# Tinyusbboard_rev4_THT.net
KiCad netlist of a schematic drawn in EAGLE
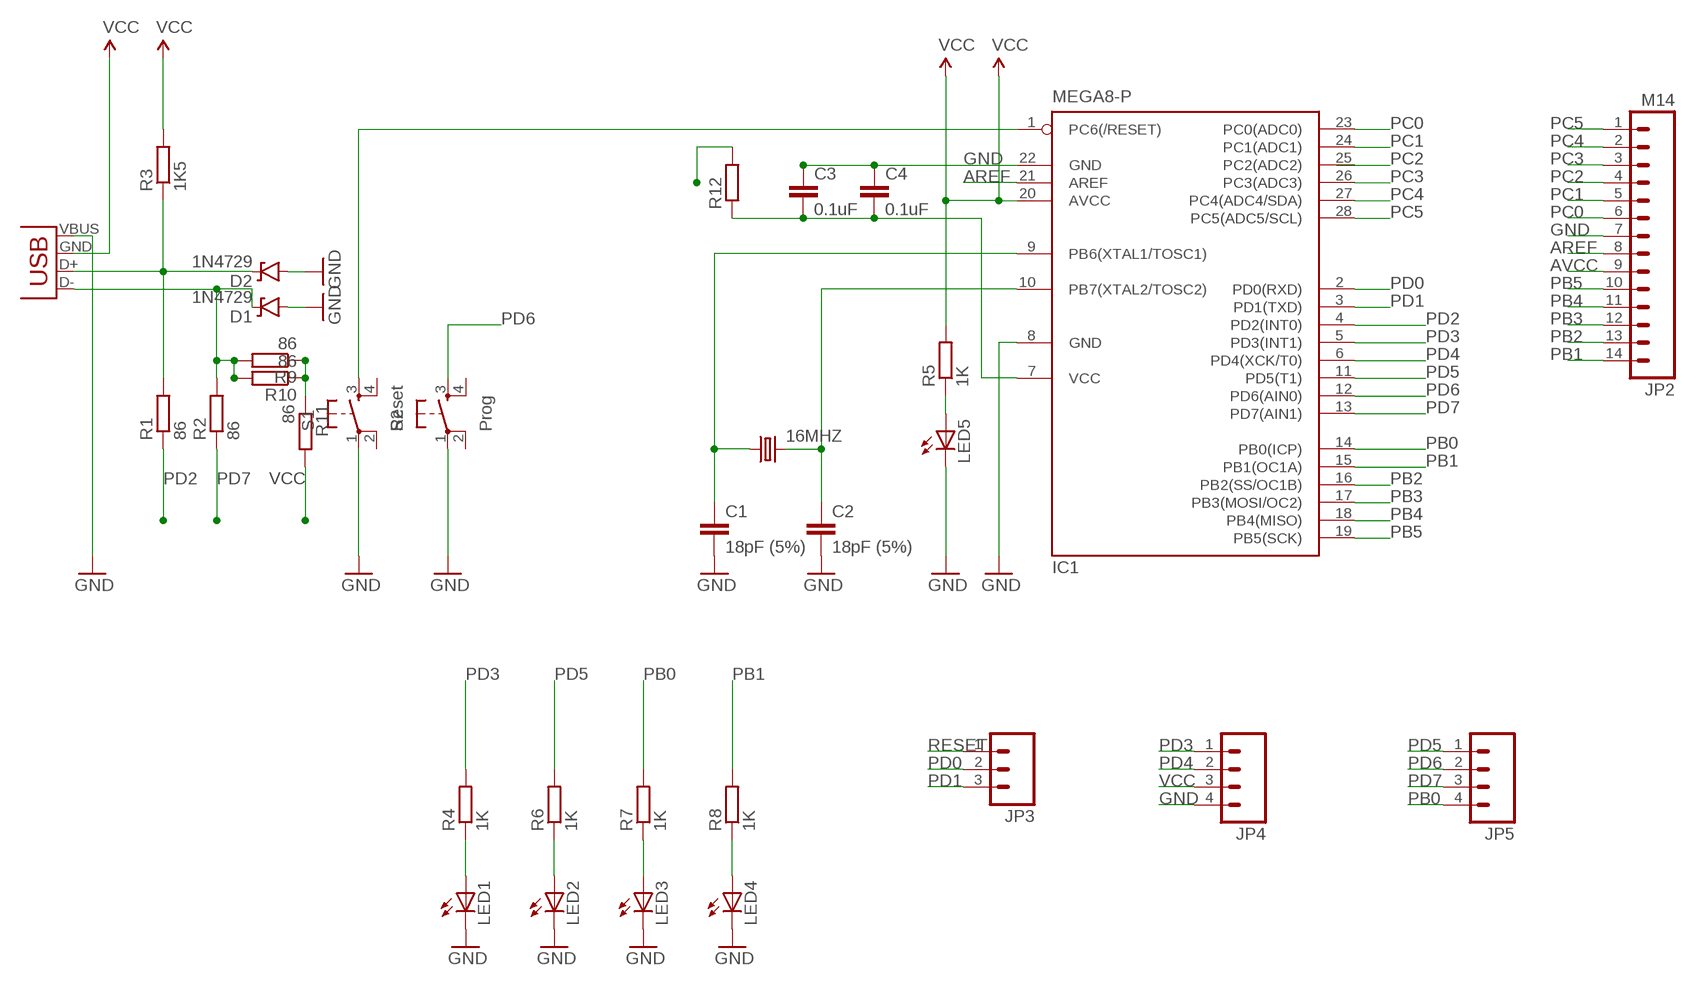
[diagram p0: schematic, sheet 1]

(export (version "E")
  (design (tool "Eeschema 10.0.6"))
  (components
    (comp (ref "16MHZ")
      (value "CRYSTALTC26V")
      (footprint "eagle-import:TC26V")
      (libsource (lib "eagle-import") (part "CRYSTALTC26V"))
    )
    (comp (ref "C1")
      (value "18pF (5%)")
      (footprint "eagle-import:C025-024X044")
      (libsource (lib "eagle-import") (part "C-EU025-024X044"))
    )
    (comp (ref "C2")
      (value "18pF (5%)")
      (footprint "eagle-import:C025-024X044")
      (libsource (lib "eagle-import") (part "C-EU025-024X044"))
    )
    (comp (ref "C3")
      (value "0.1uF")
      (footprint "eagle-import:C025-024X044")
      (libsource (lib "eagle-import") (part "C-EU025-024X044"))
    )
    (comp (ref "C4")
      (value "0.1uF")
      (footprint "eagle-import:C025-024X044")
      (libsource (lib "eagle-import") (part "C-EU025-024X044"))
    )
    (comp (ref "D1")
      (value "1N4729")
      (footprint "eagle-import:DIODE-ZENER")
      (libsource (lib "eagle-import") (part "DIODE-ZENERPTH"))
    )
    (comp (ref "D2")
      (value "1N4729")
      (footprint "eagle-import:DIODE-ZENER")
      (libsource (lib "eagle-import") (part "DIODE-ZENERPTH"))
    )
    (comp (ref "IC1")
      (value "MEGA8-P")
      (footprint "eagle-import:DIL28-3")
      (libsource (lib "eagle-import") (part "MEGA8-P"))
    )
    (comp (ref "JP1")
      (value "USB-A-H")
      (footprint "eagle-import:USB-A-H")
      (libsource (lib "eagle-import") (part "USB-A-H"))
    )
    (comp (ref "JP2")
      (value "M14")
      (footprint "eagle-import:1X14")
      (libsource (lib "eagle-import") (part "M14"))
    )
    (comp (ref "JP3")
      (value "M03PTH")
      (footprint "eagle-import:1X03")
      (libsource (lib "eagle-import") (part "M03PTH"))
    )
    (comp (ref "JP4")
      (value "M04PTH")
      (footprint "eagle-import:1X04")
      (libsource (lib "eagle-import") (part "M04PTH"))
    )
    (comp (ref "JP5")
      (value "M04PTH")
      (footprint "eagle-import:1X04")
      (libsource (lib "eagle-import") (part "M04PTH"))
    )
    (comp (ref "LED1")
      (value "LED3MM")
      (footprint "eagle-import:LED3MM")
      (libsource (lib "eagle-import") (part "LED3MM"))
    )
    (comp (ref "LED2")
      (value "LED3MM")
      (footprint "eagle-import:LED3MM")
      (libsource (lib "eagle-import") (part "LED3MM"))
    )
    (comp (ref "LED3")
      (value "LED3MM")
      (footprint "eagle-import:LED3MM")
      (libsource (lib "eagle-import") (part "LED3MM"))
    )
    (comp (ref "LED4")
      (value "LED3MM")
      (footprint "eagle-import:LED3MM")
      (libsource (lib "eagle-import") (part "LED3MM"))
    )
    (comp (ref "LED5")
      (value "LED3MM")
      (footprint "eagle-import:LED3MM")
      (libsource (lib "eagle-import") (part "LED3MM"))
    )
    (comp (ref "R1")
      (value "86")
      (footprint "eagle-import:0204_7")
      (libsource (lib "eagle-import") (part "R-EU_0204/7"))
    )
    (comp (ref "R2")
      (value "86")
      (footprint "eagle-import:0204_7")
      (libsource (lib "eagle-import") (part "R-EU_0204/7"))
    )
    (comp (ref "R3")
      (value "1K5")
      (footprint "eagle-import:0204_7")
      (libsource (lib "eagle-import") (part "R-EU_0204/7"))
    )
    (comp (ref "R4")
      (value "1K")
      (footprint "eagle-import:0204_7")
      (libsource (lib "eagle-import") (part "R-EU_0204/7"))
    )
    (comp (ref "R5")
      (value "1K")
      (footprint "eagle-import:0204_7")
      (libsource (lib "eagle-import") (part "R-EU_0204/7"))
    )
    (comp (ref "R6")
      (value "1K")
      (footprint "eagle-import:0204V")
      (libsource (lib "eagle-import") (part "R-EU_0204/2V"))
    )
    (comp (ref "R7")
      (value "1K")
      (footprint "eagle-import:0204_7")
      (libsource (lib "eagle-import") (part "R-EU_0204/7"))
    )
    (comp (ref "R8")
      (value "1K")
      (footprint "eagle-import:0204_7")
      (libsource (lib "eagle-import") (part "R-EU_0204/7"))
    )
    (comp (ref "R9")
      (value "86")
      (footprint "eagle-import:0204_7")
      (libsource (lib "eagle-import") (part "R-EU_0204/7"))
    )
    (comp (ref "R10")
      (value "86")
      (footprint "eagle-import:0204_7")
      (libsource (lib "eagle-import") (part "R-EU_0204/7"))
    )
    (comp (ref "R11")
      (value "86")
      (footprint "eagle-import:0204_7")
      (libsource (lib "eagle-import") (part "R-EU_0204/7"))
    )
    (comp (ref "R12")
      (value "R-EU_0204/7")
      (footprint "eagle-import:0204_7")
      (libsource (lib "eagle-import") (part "R-EU_0204/7"))
    )
    (comp (ref "S1")
      (value "Reset")
      (footprint "eagle-import:TACTILE-PTH")
      (libsource (lib "eagle-import") (part "TAC_SWITCHPTH"))
    )
    (comp (ref "S2")
      (value "Prog")
      (footprint "eagle-import:TACTILE-PTH")
      (libsource (lib "eagle-import") (part "TAC_SWITCHPTH"))
    )
  )
  (nets
    (net (code "1") (name "/AREF") (class "Default")
      (node (ref "IC1") (pin "21") (pinfunction "AREF_21") (pintype "passive"))
      (node (ref "JP2") (pin "8") (pinfunction "8_8") (pintype "passive"))
    )
    (net (code "2") (name "/AVCC") (class "Default")
      (node (ref "JP2") (pin "9") (pinfunction "9_9") (pintype "passive"))
    )
    (net (code "3") (name "/PB0") (class "Default")
      (node (ref "IC1") (pin "14") (pinfunction "PB0(ICP)_14") (pintype "bidirectional"))
      (node (ref "JP5") (pin "4") (pinfunction "4_4") (pintype "passive"))
      (node (ref "R7") (pin "2") (pinfunction "2_2") (pintype "passive"))
    )
    (net (code "4") (name "/PB1") (class "Default")
      (node (ref "IC1") (pin "15") (pinfunction "PB1(OC1A)_15") (pintype "bidirectional"))
      (node (ref "JP2") (pin "14") (pinfunction "14_14") (pintype "passive"))
      (node (ref "R8") (pin "2") (pinfunction "2_2") (pintype "passive"))
    )
    (net (code "5") (name "/PB2") (class "Default")
      (node (ref "IC1") (pin "16") (pinfunction "PB2(SS/OC1B)_16") (pintype "bidirectional"))
      (node (ref "JP2") (pin "13") (pinfunction "13_13") (pintype "passive"))
    )
    (net (code "6") (name "/PB3") (class "Default")
      (node (ref "IC1") (pin "17") (pinfunction "PB3(MOSI/OC2)_17") (pintype "bidirectional"))
      (node (ref "JP2") (pin "12") (pinfunction "12_12") (pintype "passive"))
    )
    (net (code "7") (name "/PB4") (class "Default")
      (node (ref "IC1") (pin "18") (pinfunction "PB4(MISO)_18") (pintype "bidirectional"))
      (node (ref "JP2") (pin "11") (pinfunction "11_11") (pintype "passive"))
    )
    (net (code "8") (name "/PB5") (class "Default")
      (node (ref "IC1") (pin "19") (pinfunction "PB5(SCK)_19") (pintype "bidirectional"))
      (node (ref "JP2") (pin "10") (pinfunction "10_10") (pintype "passive"))
    )
    (net (code "9") (name "/PC0") (class "Default")
      (node (ref "IC1") (pin "23") (pinfunction "PC0(ADC0)_23") (pintype "bidirectional"))
      (node (ref "JP2") (pin "6") (pinfunction "6_6") (pintype "passive"))
    )
    (net (code "10") (name "/PC1") (class "Default")
      (node (ref "IC1") (pin "24") (pinfunction "PC1(ADC1)_24") (pintype "bidirectional"))
      (node (ref "JP2") (pin "5") (pinfunction "5_5") (pintype "passive"))
    )
    (net (code "11") (name "/PC2") (class "Default")
      (node (ref "IC1") (pin "25") (pinfunction "PC2(ADC2)_25") (pintype "bidirectional"))
      (node (ref "JP2") (pin "4") (pinfunction "4_4") (pintype "passive"))
    )
    (net (code "12") (name "/PC3") (class "Default")
      (node (ref "IC1") (pin "26") (pinfunction "PC3(ADC3)_26") (pintype "bidirectional"))
      (node (ref "JP2") (pin "3") (pinfunction "3_3") (pintype "passive"))
    )
    (net (code "13") (name "/PC4") (class "Default")
      (node (ref "IC1") (pin "27") (pinfunction "PC4(ADC4/SDA)_27") (pintype "bidirectional"))
      (node (ref "JP2") (pin "2") (pinfunction "2_2") (pintype "passive"))
    )
    (net (code "14") (name "/PC5") (class "Default")
      (node (ref "IC1") (pin "28") (pinfunction "PC5(ADC5/SCL)_28") (pintype "bidirectional"))
      (node (ref "JP2") (pin "1") (pinfunction "1_1") (pintype "passive"))
    )
    (net (code "15") (name "/PD0") (class "Default")
      (node (ref "IC1") (pin "2") (pinfunction "PD0(RXD)_2") (pintype "bidirectional"))
      (node (ref "JP3") (pin "2") (pinfunction "2_2") (pintype "passive"))
    )
    (net (code "16") (name "/PD1") (class "Default")
      (node (ref "IC1") (pin "3") (pinfunction "PD1(TXD)_3") (pintype "bidirectional"))
      (node (ref "JP3") (pin "3") (pinfunction "3_3") (pintype "passive"))
    )
    (net (code "17") (name "/PD2") (class "Default")
      (node (ref "IC1") (pin "4") (pinfunction "PD2(INT0)_4") (pintype "bidirectional"))
      (node (ref "R1") (pin "1") (pinfunction "1_1") (pintype "passive"))
    )
    (net (code "18") (name "/PD3") (class "Default")
      (node (ref "IC1") (pin "5") (pinfunction "PD3(INT1)_5") (pintype "bidirectional"))
      (node (ref "JP4") (pin "1") (pinfunction "1_1") (pintype "passive"))
      (node (ref "R4") (pin "2") (pinfunction "2_2") (pintype "passive"))
    )
    (net (code "19") (name "/PD4") (class "Default")
      (node (ref "IC1") (pin "6") (pinfunction "PD4(XCK/T0)_6") (pintype "bidirectional"))
      (node (ref "JP4") (pin "2") (pinfunction "2_2") (pintype "passive"))
    )
    (net (code "20") (name "/PD5") (class "Default")
      (node (ref "IC1") (pin "11") (pinfunction "PD5(T1)_11") (pintype "bidirectional"))
      (node (ref "JP5") (pin "1") (pinfunction "1_1") (pintype "passive"))
      (node (ref "R6") (pin "2") (pinfunction "2_2") (pintype "passive"))
    )
    (net (code "21") (name "/PD6") (class "Default")
      (node (ref "IC1") (pin "12") (pinfunction "PD6(AIN0)_12") (pintype "bidirectional"))
      (node (ref "JP5") (pin "2") (pinfunction "2_2") (pintype "passive"))
      (node (ref "S2") (pin "3") (pinfunction "3_3") (pintype "passive"))
    )
    (net (code "22") (name "/PD7") (class "Default")
      (node (ref "IC1") (pin "13") (pinfunction "PD7(AIN1)_13") (pintype "bidirectional"))
      (node (ref "JP5") (pin "3") (pinfunction "3_3") (pintype "passive"))
      (node (ref "R2") (pin "1") (pinfunction "1_1") (pintype "passive"))
    )
    (net (code "23") (name "/RESET") (class "Default")
      (node (ref "IC1") (pin "1") (pinfunction "PC6(/RESET)_1") (pintype "bidirectional"))
      (node (ref "JP3") (pin "1") (pinfunction "1_1") (pintype "passive"))
      (node (ref "R12") (pin "2") (pinfunction "2_2") (pintype "passive"))
      (node (ref "S1") (pin "3") (pinfunction "3_3") (pintype "passive"))
    )
    (net (code "24") (name "GND") (class "Default")
      (node (ref "C1") (pin "2") (pinfunction "2_2") (pintype "passive"))
      (node (ref "C2") (pin "2") (pinfunction "2_2") (pintype "passive"))
      (node (ref "C3") (pin "1") (pinfunction "1_1") (pintype "passive"))
      (node (ref "C4") (pin "1") (pinfunction "1_1") (pintype "passive"))
      (node (ref "D1") (pin "P$2") (pinfunction "A_P$2") (pintype "passive"))
      (node (ref "D2") (pin "P$2") (pinfunction "A_P$2") (pintype "passive"))
      (node (ref "IC1") (pin "22") (pinfunction "GND_22") (pintype "power_in"))
      (node (ref "IC1") (pin "8") (pinfunction "GND_8") (pintype "power_in"))
      (node (ref "JP1") (pin "VBUS") (pinfunction "GND_VBUS") (pintype "bidirectional"))
      (node (ref "JP2") (pin "7") (pinfunction "7_7") (pintype "passive"))
      (node (ref "JP4") (pin "4") (pinfunction "4_4") (pintype "passive"))
      (node (ref "LED1") (pin "K") (pinfunction "C_K") (pintype "passive"))
      (node (ref "LED2") (pin "K") (pinfunction "C_K") (pintype "passive"))
      (node (ref "LED3") (pin "K") (pinfunction "C_K") (pintype "passive"))
      (node (ref "LED4") (pin "K") (pinfunction "C_K") (pintype "passive"))
      (node (ref "LED5") (pin "K") (pinfunction "C_K") (pintype "passive"))
      (node (ref "S1") (pin "1") (pinfunction "1_1") (pintype "passive"))
      (node (ref "S2") (pin "1") (pinfunction "1_1") (pintype "passive"))
    )
    (net (code "25") (name "Net-(D1-C)") (class "Default")
      (node (ref "D1") (pin "P$1") (pinfunction "C_P$1") (pintype "passive"))
      (node (ref "JP1") (pin "D-") (pinfunction "D+_D-") (pintype "bidirectional"))
      (node (ref "R10") (pin "2") (pinfunction "2_2") (pintype "passive"))
      (node (ref "R2") (pin "2") (pinfunction "2_2") (pintype "passive"))
      (node (ref "R9") (pin "2") (pinfunction "2_2") (pintype "passive"))
    )
    (net (code "26") (name "Net-(D2-C)") (class "Default")
      (node (ref "D2") (pin "P$1") (pinfunction "C_P$1") (pintype "passive"))
      (node (ref "JP1") (pin "D+") (pinfunction "D-_D+") (pintype "bidirectional"))
      (node (ref "R1") (pin "2") (pinfunction "2_2") (pintype "passive"))
      (node (ref "R3") (pin "1") (pinfunction "1_1") (pintype "passive"))
    )
    (net (code "27") (name "Net-(IC1-PB6(XTAL1{slash}TOSC1))") (class "Default")
      (node (ref "16MHZ") (pin "1") (pinfunction "1_1") (pintype "passive"))
      (node (ref "C1") (pin "1") (pinfunction "1_1") (pintype "passive"))
      (node (ref "IC1") (pin "9") (pinfunction "PB6(XTAL1/TOSC1)_9") (pintype "bidirectional"))
    )
    (net (code "28") (name "Net-(IC1-PB7(XTAL2{slash}TOSC2))") (class "Default")
      (node (ref "16MHZ") (pin "2") (pinfunction "2_2") (pintype "passive"))
      (node (ref "C2") (pin "1") (pinfunction "1_1") (pintype "passive"))
      (node (ref "IC1") (pin "10") (pinfunction "PB7(XTAL2/TOSC2)_10") (pintype "bidirectional"))
    )
    (net (code "29") (name "Net-(LED1-PadA)") (class "Default")
      (node (ref "LED1") (pin "A") (pinfunction "A_A") (pintype "passive"))
      (node (ref "R4") (pin "1") (pinfunction "1_1") (pintype "passive"))
    )
    (net (code "30") (name "Net-(LED2-PadA)") (class "Default")
      (node (ref "LED2") (pin "A") (pinfunction "A_A") (pintype "passive"))
      (node (ref "R6") (pin "1") (pinfunction "1_1") (pintype "passive"))
    )
    (net (code "31") (name "Net-(LED3-PadA)") (class "Default")
      (node (ref "LED3") (pin "A") (pinfunction "A_A") (pintype "passive"))
      (node (ref "R7") (pin "1") (pinfunction "1_1") (pintype "passive"))
    )
    (net (code "32") (name "Net-(LED4-PadA)") (class "Default")
      (node (ref "LED4") (pin "A") (pinfunction "A_A") (pintype "passive"))
      (node (ref "R8") (pin "1") (pinfunction "1_1") (pintype "passive"))
    )
    (net (code "33") (name "Net-(LED5-PadA)") (class "Default")
      (node (ref "LED5") (pin "A") (pinfunction "A_A") (pintype "passive"))
      (node (ref "R5") (pin "1") (pinfunction "1_1") (pintype "passive"))
    )
    (net (code "34") (name "Net-(R10-Pad1)") (class "Default")
      (node (ref "R10") (pin "1") (pinfunction "1_1") (pintype "passive"))
      (node (ref "R11") (pin "1") (pinfunction "1_1") (pintype "passive"))
      (node (ref "R9") (pin "1") (pinfunction "1_1") (pintype "passive"))
    )
    (net (code "35") (name "VCC") (class "Default")
      (node (ref "C3") (pin "2") (pinfunction "2_2") (pintype "passive"))
      (node (ref "C4") (pin "2") (pinfunction "2_2") (pintype "passive"))
      (node (ref "IC1") (pin "20") (pinfunction "AVCC_20") (pintype "power_in"))
      (node (ref "IC1") (pin "7") (pinfunction "VCC_7") (pintype "power_in"))
      (node (ref "JP1") (pin "GND") (pinfunction "VBUS_GND") (pintype "bidirectional"))
      (node (ref "JP4") (pin "3") (pinfunction "3_3") (pintype "passive"))
      (node (ref "R11") (pin "2") (pinfunction "2_2") (pintype "passive"))
      (node (ref "R12") (pin "1") (pinfunction "1_1") (pintype "passive"))
      (node (ref "R3") (pin "2") (pinfunction "2_2") (pintype "passive"))
      (node (ref "R5") (pin "2") (pinfunction "2_2") (pintype "passive"))
    )
    (net (code "36") (name "unconnected-(S1-Pad2)") (class "Default")
      (node (ref "S1") (pin "2") (pinfunction "2_2") (pintype "passive"))
    )
    (net (code "37") (name "unconnected-(S1-Pad4)") (class "Default")
      (node (ref "S1") (pin "4") (pinfunction "4_4") (pintype "passive"))
    )
    (net (code "38") (name "unconnected-(S2-Pad2)") (class "Default")
      (node (ref "S2") (pin "2") (pinfunction "2_2") (pintype "passive"))
    )
    (net (code "39") (name "unconnected-(S2-Pad4)") (class "Default")
      (node (ref "S2") (pin "4") (pinfunction "4_4") (pintype "passive"))
    )
  )
)
